# main_board2.net
KiCad netlist of a schematic drawn in Altium Designer
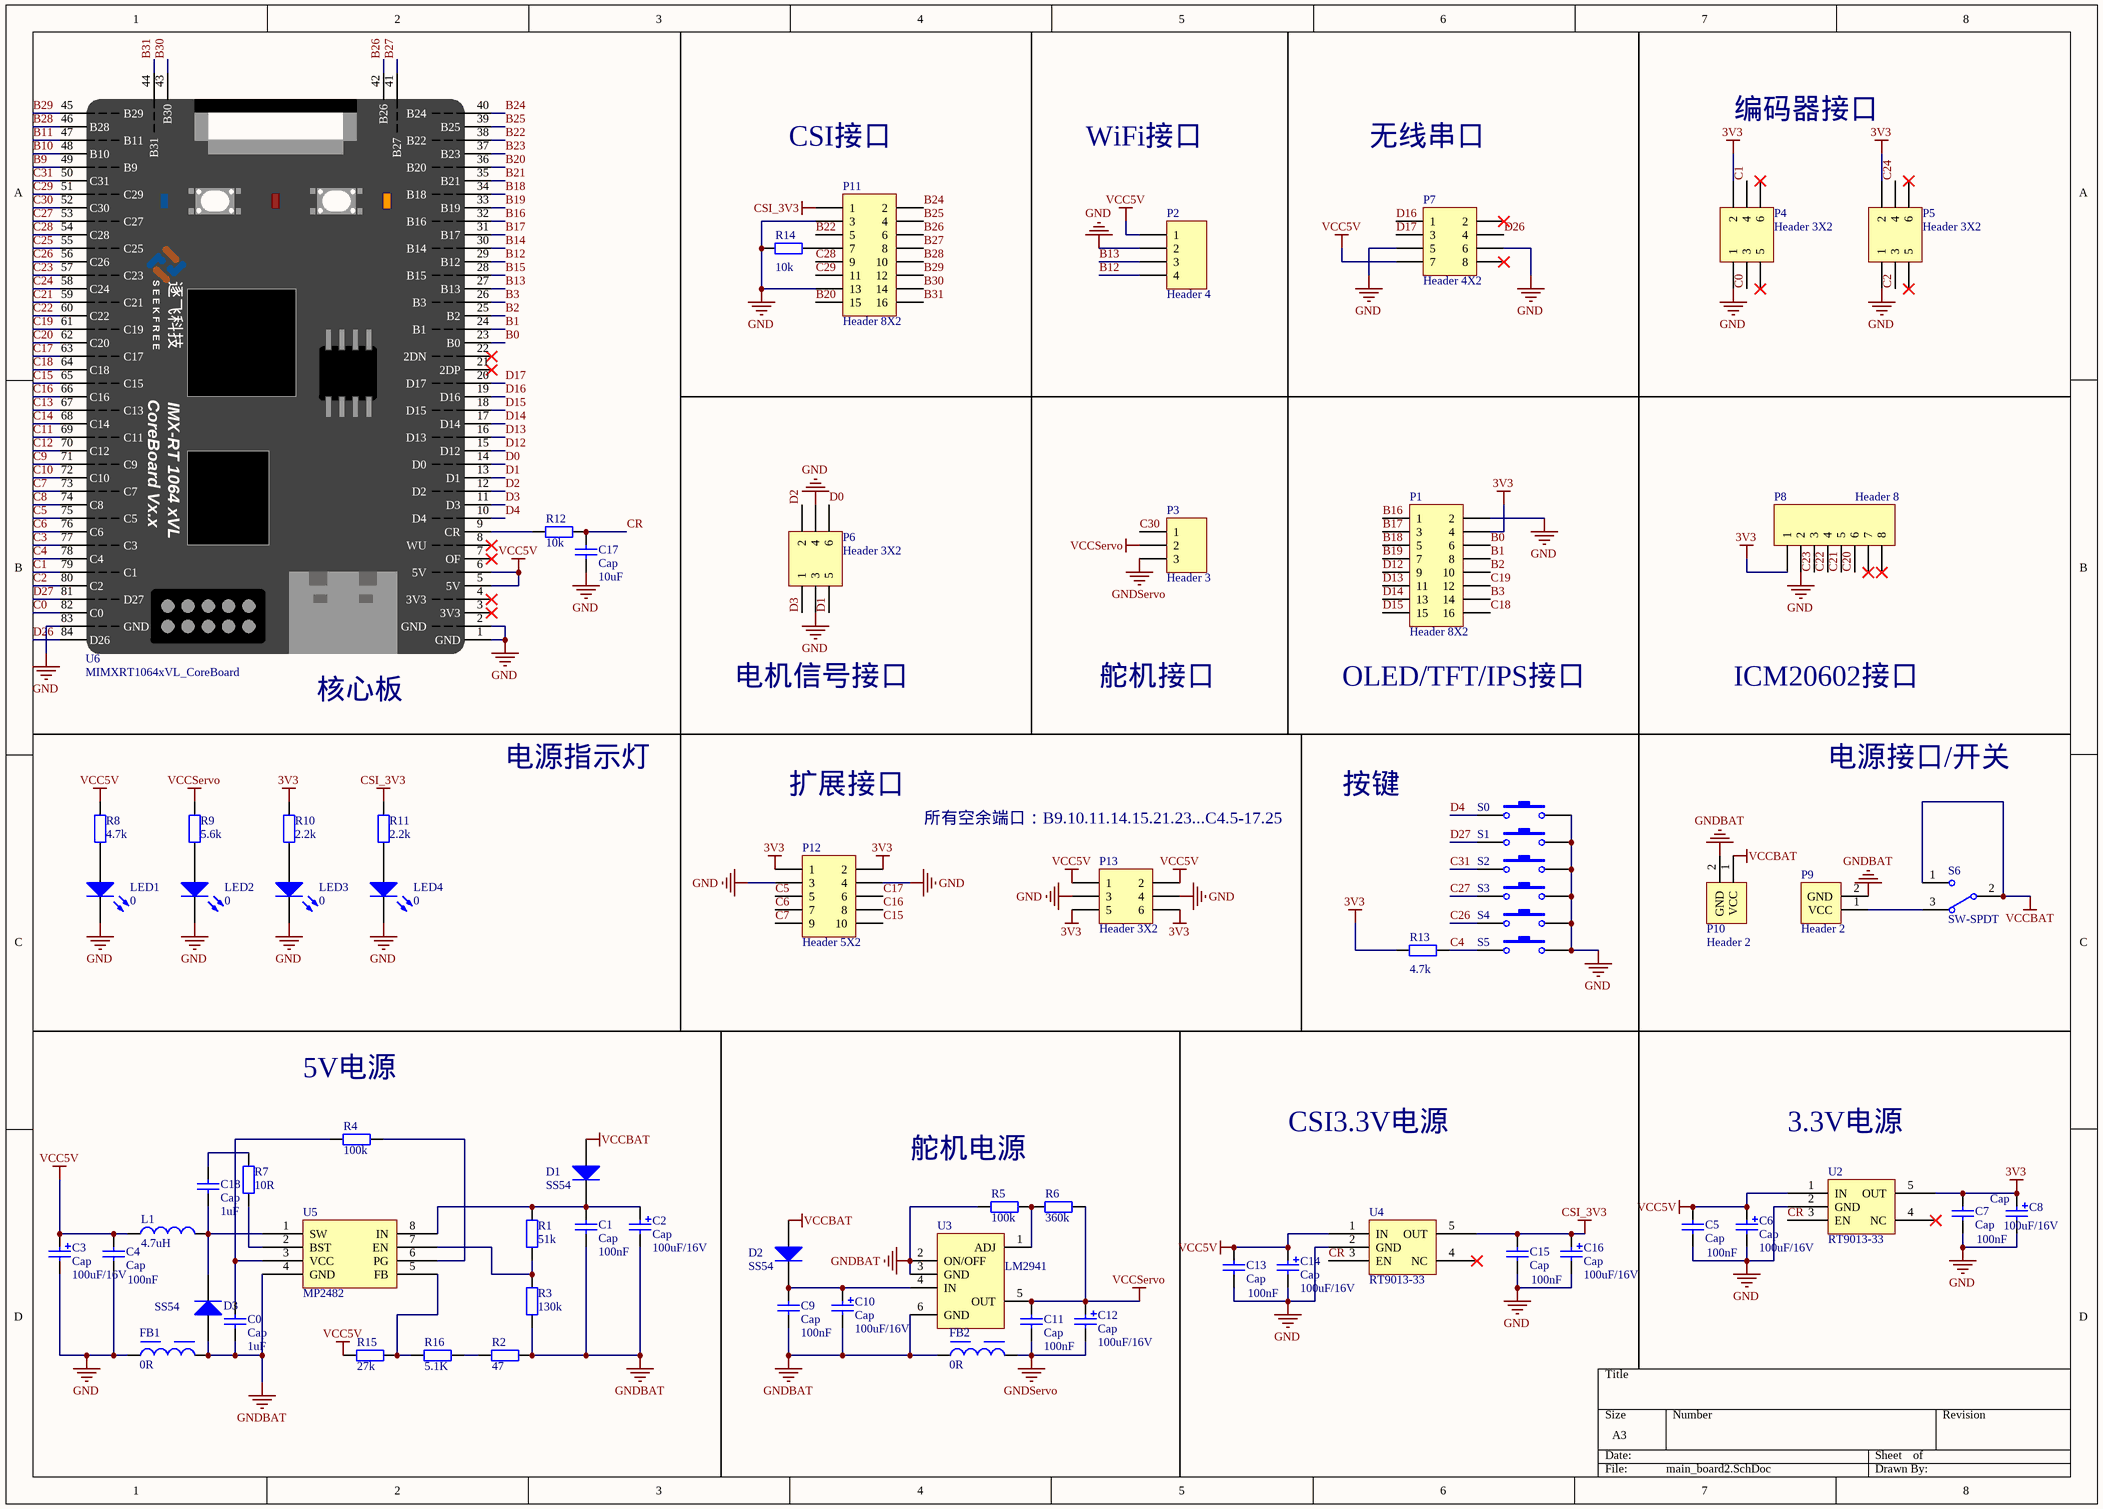
[diagram p0: main_board2.SchDoc]

(export (version "E")
  (design (tool "Eeschema 10.0.6"))
  (components
    (comp (ref "C0")
      (value "Cap")
      (footprint "0603C")
      (description "Capacitor")
      (fields (field (name "ALTIUM_VALUE") "1uF") (field (name "PUBLISHER") "Altium Limited"))
      (libsource (lib "Schlib1") (part "Cap"))
    )
    (comp (ref "C1")
      (value "Cap")
      (footprint "0603C")
      (description "Capacitor")
      (fields (field (name "ALTIUM_VALUE") "100nF") (field (name "PUBLISHER") "Altium Limited"))
      (libsource (lib "Schlib1") (part "Cap"))
    )
    (comp (ref "C2")
      (value "Cap")
      (footprint "电解电容")
      (description "Capacitor")
      (fields (field (name "ALTIUM_VALUE") "100uF/16V") (field (name "PUBLISHER") "Altium Limited"))
      (libsource (lib "Schlib1") (part "Cap2"))
    )
    (comp (ref "C3")
      (value "Cap")
      (footprint "电解电容")
      (description "Capacitor")
      (fields (field (name "ALTIUM_VALUE") "100uF/16V") (field (name "PUBLISHER") "Altium Limited"))
      (libsource (lib "Schlib1") (part "Cap2"))
    )
    (comp (ref "C4")
      (value "Cap")
      (footprint "0603C")
      (description "Capacitor")
      (fields (field (name "ALTIUM_VALUE") "100nF") (field (name "PUBLISHER") "Altium Limited"))
      (libsource (lib "Schlib1") (part "Cap"))
    )
    (comp (ref "C5")
      (value "Cap")
      (footprint "0603C")
      (description "Capacitor")
      (fields (field (name "ALTIUM_VALUE") "100nF") (field (name "PUBLISHER") "Altium Limited"))
      (libsource (lib "Schlib1") (part "Cap"))
    )
    (comp (ref "C6")
      (value "Cap")
      (footprint "电解电容")
      (description "Capacitor")
      (fields (field (name "ALTIUM_VALUE") "100uF/16V") (field (name "PUBLISHER") "Altium Limited"))
      (libsource (lib "Schlib1") (part "Cap2"))
    )
    (comp (ref "C7")
      (value "Cap")
      (footprint "0603C")
      (description "Capacitor")
      (fields (field (name "ALTIUM_VALUE") "100nF") (field (name "PUBLISHER") "Altium Limited"))
      (libsource (lib "Schlib1") (part "Cap"))
    )
    (comp (ref "C8")
      (value "Cap")
      (footprint "电解电容")
      (description "Capacitor")
      (fields (field (name "ALTIUM_VALUE") "100uF/16V") (field (name "PUBLISHER") "Altium Limited"))
      (libsource (lib "Schlib1") (part "Cap2"))
    )
    (comp (ref "C9")
      (value "Cap")
      (footprint "0603C")
      (description "Capacitor")
      (fields (field (name "ALTIUM_VALUE") "100nF") (field (name "PUBLISHER") "Altium Limited"))
      (libsource (lib "Schlib1") (part "Cap"))
    )
    (comp (ref "C10")
      (value "Cap")
      (footprint "电解电容")
      (description "Capacitor")
      (fields (field (name "ALTIUM_VALUE") "100uF/16V") (field (name "PUBLISHER") "Altium Limited"))
      (libsource (lib "Schlib1") (part "Cap2"))
    )
    (comp (ref "C11")
      (value "Cap")
      (footprint "0603C")
      (description "Capacitor")
      (fields (field (name "ALTIUM_VALUE") "100nF") (field (name "PUBLISHER") "Altium Limited"))
      (libsource (lib "Schlib1") (part "Cap"))
    )
    (comp (ref "C12")
      (value "Cap")
      (footprint "电解电容")
      (description "Capacitor")
      (fields (field (name "ALTIUM_VALUE") "100uF/16V") (field (name "PUBLISHER") "Altium Limited"))
      (libsource (lib "Schlib1") (part "Cap2"))
    )
    (comp (ref "C13")
      (value "Cap")
      (footprint "0603C")
      (description "Capacitor")
      (fields (field (name "ALTIUM_VALUE") "100nF") (field (name "PUBLISHER") "Altium Limited"))
      (libsource (lib "Schlib1") (part "Cap"))
    )
    (comp (ref "C14")
      (value "Cap")
      (footprint "电解电容")
      (description "Capacitor")
      (fields (field (name "ALTIUM_VALUE") "100uF/16V") (field (name "PUBLISHER") "Altium Limited"))
      (libsource (lib "Schlib1") (part "Cap2"))
    )
    (comp (ref "C15")
      (value "Cap")
      (footprint "0603C")
      (description "Capacitor")
      (fields (field (name "ALTIUM_VALUE") "100nF") (field (name "PUBLISHER") "Altium Limited"))
      (libsource (lib "Schlib1") (part "Cap"))
    )
    (comp (ref "C16")
      (value "Cap")
      (footprint "电解电容")
      (description "Capacitor")
      (fields (field (name "ALTIUM_VALUE") "100uF/16V") (field (name "PUBLISHER") "Altium Limited"))
      (libsource (lib "Schlib1") (part "Cap2"))
    )
    (comp (ref "C17")
      (value "Cap")
      (footprint "0603C")
      (description "Capacitor")
      (fields (field (name "ALTIUM_VALUE") "10uF") (field (name "PUBLISHER") "Altium Limited"))
      (libsource (lib "Schlib1") (part "Cap"))
    )
    (comp (ref "C18")
      (value "Cap")
      (footprint "0603C")
      (description "Capacitor")
      (fields (field (name "ALTIUM_VALUE") "1uF") (field (name "PUBLISHER") "Altium Limited"))
      (libsource (lib "Schlib1") (part "Cap"))
    )
    (comp (ref "D1")
      (value "SS54")
      (footprint "ss54")
      (description "Default Diode")
      (fields (field (name "PUBLISHER") "Altium Limited"))
      (libsource (lib "Schlib1") (part "Diode_1"))
    )
    (comp (ref "D2")
      (value "SS54")
      (footprint "ss54")
      (description "Default Diode")
      (fields (field (name "PUBLISHER") "Altium Limited"))
      (libsource (lib "Schlib1") (part "Diode_1"))
    )
    (comp (ref "D3")
      (value "SS54")
      (footprint "ss54")
      (description "Default Diode")
      (fields (field (name "PUBLISHER") "Altium Limited"))
      (libsource (lib "Schlib1") (part "Diode_1"))
    )
    (comp (ref "FB1")
      (value "0R")
      (footprint "0805")
      (description "Inductor")
      (fields (field (name "PUBLISHER") "Altium Limited"))
      (libsource (lib "Schlib1") (part "FB"))
    )
    (comp (ref "FB2")
      (value "0R")
      (footprint "0805")
      (description "Inductor")
      (fields (field (name "PUBLISHER") "Altium Limited"))
      (libsource (lib "Schlib1") (part "FB"))
    )
    (comp (ref "L1")
      (value "4.7uH")
      (footprint "CD73")
      (description "Inductor")
      (fields (field (name "PUBLISHER") "Altium Limited"))
      (libsource (lib "Schlib1") (part "Inductor_2"))
    )
    (comp (ref "LED1")
      (value "0")
      (footprint "0603C")
      (description "Typical RED, GREEN, YELLOW, AMBER GaAs LED")
      (fields (field (name "PUBLISHER") "Altium Limited"))
      (libsource (lib "Schlib1") (part "LED2"))
    )
    (comp (ref "LED2")
      (value "0")
      (footprint "0603C")
      (description "Typical RED, GREEN, YELLOW, AMBER GaAs LED")
      (fields (field (name "PUBLISHER") "Altium Limited"))
      (libsource (lib "Schlib1") (part "LED2"))
    )
    (comp (ref "LED3")
      (value "0")
      (footprint "0603C")
      (description "Typical RED, GREEN, YELLOW, AMBER GaAs LED")
      (fields (field (name "PUBLISHER") "Altium Limited"))
      (libsource (lib "Schlib1") (part "LED2"))
    )
    (comp (ref "LED4")
      (value "0")
      (footprint "0603C")
      (description "Typical RED, GREEN, YELLOW, AMBER GaAs LED")
      (fields (field (name "PUBLISHER") "Altium Limited"))
      (libsource (lib "Schlib1") (part "LED2"))
    )
    (comp (ref "P1")
      (value "Header 8X2")
      (footprint "HDR2X8")
      (description "Header, 8-Pin, Dual row")
      (fields (field (name "PUBLISHER") "Altium Limited"))
      (libsource (lib "Miscellaneous Connectors") (part "Header 8X2"))
    )
    (comp (ref "P2")
      (value "Header 4")
      (footprint "HDR1X4")
      (description "Header, 4-Pin")
      (fields (field (name "PUBLISHER") "Altium Limited"))
      (libsource (lib "Miscellaneous Connectors") (part "Header 4"))
    )
    (comp (ref "P3")
      (value "Header 3")
      (footprint "HDR1X3")
      (description "Header, 3-Pin")
      (fields (field (name "PUBLISHER") "Altium Limited"))
      (libsource (lib "Miscellaneous Connectors") (part "Header 3"))
    )
    (comp (ref "P4")
      (value "Header 3X2")
      (footprint "HDR2X3")
      (description "Header, 3-Pin, Dual row")
      (fields (field (name "PUBLISHER") "Altium Limited"))
      (libsource (lib "Miscellaneous Connectors") (part "Header 3X2"))
    )
    (comp (ref "P5")
      (value "Header 3X2")
      (footprint "HDR2X3")
      (description "Header, 3-Pin, Dual row")
      (fields (field (name "PUBLISHER") "Altium Limited"))
      (libsource (lib "Miscellaneous Connectors") (part "Header 3X2"))
    )
    (comp (ref "P6")
      (value "Header 3X2")
      (footprint "HDR2X3")
      (description "Header, 3-Pin, Dual row")
      (fields (field (name "PUBLISHER") "Altium Limited"))
      (libsource (lib "Miscellaneous Connectors") (part "Header 3X2"))
    )
    (comp (ref "P7")
      (value "Header 4X2")
      (footprint "HDR2X4")
      (description "Header, 4-Pin, Dual row")
      (fields (field (name "PUBLISHER") "Altium Limited"))
      (libsource (lib "Miscellaneous Connectors") (part "Header 4X2"))
    )
    (comp (ref "P8")
      (value "Header 8")
      (footprint "HDR1X8")
      (description "Header, 8-Pin")
      (fields (field (name "PUBLISHER") "Altium Limited"))
      (libsource (lib "Miscellaneous Connectors") (part "Header 8"))
    )
    (comp (ref "P9")
      (value "Header 2")
      (footprint "VCCBAT")
      (description "Header, 2-Pin")
      (fields (field (name "PUBLISHER") "Altium Limited"))
      (libsource (lib "Schlib1") (part "Header 2_1"))
    )
    (comp (ref "P10")
      (value "Header 2")
      (footprint "VCCBAT")
      (description "Header, 2-Pin")
      (fields (field (name "PUBLISHER") "Altium Limited"))
      (libsource (lib "Schlib1") (part "Header 2_2"))
    )
    (comp (ref "P11")
      (value "Header 8X2")
      (footprint "HDR2X8")
      (description "Header, 8-Pin, Dual row")
      (fields (field (name "PUBLISHER") "Altium Limited"))
      (libsource (lib "Miscellaneous Connectors") (part "Header 8X2"))
    )
    (comp (ref "P12")
      (value "Header 5X2")
      (footprint "HDR2X5")
      (description "Header, 5-Pin, Dual row")
      (fields (field (name "PUBLISHER") "Altium Limited"))
      (libsource (lib "Miscellaneous Connectors") (part "Header 5X2"))
    )
    (comp (ref "P13")
      (value "Header 3X2")
      (footprint "HDR2X3")
      (description "Header, 3-Pin, Dual row")
      (fields (field (name "PUBLISHER") "Altium Limited"))
      (libsource (lib "") (part "Header 3X2_1"))
    )
    (comp (ref "R1")
      (value "51k")
      (footprint "0603R")
      (description "Resistor")
      (fields (field (name "Comment") "Res2") (field (name "PUBLISHER") "Altium Limited"))
      (libsource (lib "") (part "Res2_2"))
    )
    (comp (ref "R2")
      (value "47")
      (footprint "0603R")
      (description "Resistor")
      (fields (field (name "Comment") "Res2") (field (name "PUBLISHER") "Altium Limited"))
      (libsource (lib "Schlib1") (part "Res2"))
    )
    (comp (ref "R3")
      (value "130k")
      (footprint "0603R")
      (description "Resistor 改成了120k")
      (fields (field (name "Comment") "Res2") (field (name "PUBLISHER") "Altium Limited"))
      (libsource (lib "") (part "Res2_2"))
    )
    (comp (ref "R4")
      (value "100k")
      (footprint "0603R")
      (description "Resistor")
      (fields (field (name "Comment") "Res2") (field (name "PUBLISHER") "Altium Limited"))
      (libsource (lib "Schlib1") (part "Res2"))
    )
    (comp (ref "R5")
      (value "100k")
      (footprint "0603R")
      (description "Resistor")
      (fields (field (name "Comment") "Res2") (field (name "PUBLISHER") "Altium Limited"))
      (libsource (lib "") (part "Res2_1"))
    )
    (comp (ref "R6")
      (value "360k")
      (footprint "0603R")
      (description "Resistor 改成了330k")
      (fields (field (name "Comment") "Res2") (field (name "PUBLISHER") "Altium Limited"))
      (libsource (lib "") (part "Res2_1"))
    )
    (comp (ref "R7")
      (value "10R")
      (footprint "0603R")
      (description "Resistor")
      (fields (field (name "Comment") "Res2") (field (name "PUBLISHER") "Altium Limited"))
      (libsource (lib "") (part "Res2_2"))
    )
    (comp (ref "R8")
      (value "4.7k")
      (footprint "0603R")
      (description "Resistor")
      (fields (field (name "Comment") "Res2") (field (name "PUBLISHER") "Altium Limited"))
      (libsource (lib "") (part "Res2_2"))
    )
    (comp (ref "R9")
      (value "5.6k")
      (footprint "0603R")
      (description "Resistor改成了5.1k")
      (fields (field (name "Comment") "Res2") (field (name "PUBLISHER") "Altium Limited"))
      (libsource (lib "") (part "Res2_2"))
    )
    (comp (ref "R10")
      (value "2.2k")
      (footprint "0603R")
      (description "Resistor")
      (fields (field (name "Comment") "Res2") (field (name "PUBLISHER") "Altium Limited"))
      (libsource (lib "") (part "Res2_2"))
    )
    (comp (ref "R11")
      (value "2.2k")
      (footprint "0603R")
      (description "Resistor")
      (fields (field (name "Comment") "Res2") (field (name "PUBLISHER") "Altium Limited"))
      (libsource (lib "") (part "Res2_2"))
    )
    (comp (ref "R12")
      (value "10k")
      (footprint "0603R")
      (description "Resistor")
      (fields (field (name "Comment") "Res2") (field (name "PUBLISHER") "Altium Limited"))
      (libsource (lib "") (part "Res2_1"))
    )
    (comp (ref "R13")
      (value "4.7k")
      (footprint "0603R")
      (description "Resistor")
      (fields (field (name "Comment") "Res2") (field (name "PUBLISHER") "Altium Limited"))
      (libsource (lib "") (part "Res2_1"))
    )
    (comp (ref "R14")
      (value "10k")
      (footprint "0603R")
      (description "Resistor")
      (fields (field (name "Comment") "Res2") (field (name "PUBLISHER") "Altium Limited"))
      (libsource (lib "") (part "Res2_1"))
    )
    (comp (ref "R15")
      (value "27k")
      (footprint "0603R")
      (description "Resistor")
      (fields (field (name "Comment") "Res2") (field (name "PUBLISHER") "Altium Limited"))
      (libsource (lib "Schlib1") (part "Res2"))
    )
    (comp (ref "R16")
      (value "5.1K")
      (footprint "0603R")
      (description "Resistor")
      (fields (field (name "Comment") "Res2") (field (name "PUBLISHER") "Altium Limited"))
      (libsource (lib "Schlib1") (part "Res2"))
    )
    (comp (ref "S0")
      (value "~")
      (footprint "SPST-2")
      (description "Switch")
      (fields (field (name "PUBLISHER") "Altium Limited"))
      (libsource (lib "Miscellaneous Devices") (part "SW-PB"))
    )
    (comp (ref "S1")
      (value "~")
      (footprint "SPST-2")
      (description "Switch")
      (fields (field (name "PUBLISHER") "Altium Limited"))
      (libsource (lib "Miscellaneous Devices") (part "SW-PB"))
    )
    (comp (ref "S2")
      (value "~")
      (footprint "SPST-2")
      (description "Switch")
      (fields (field (name "PUBLISHER") "Altium Limited"))
      (libsource (lib "Miscellaneous Devices") (part "SW-PB"))
    )
    (comp (ref "S3")
      (value "~")
      (footprint "SPST-2")
      (description "Switch")
      (fields (field (name "PUBLISHER") "Altium Limited"))
      (libsource (lib "Miscellaneous Devices") (part "SW-PB"))
    )
    (comp (ref "S4")
      (value "~")
      (footprint "SPST-2")
      (description "Switch")
      (fields (field (name "PUBLISHER") "Altium Limited"))
      (libsource (lib "Miscellaneous Devices") (part "SW-PB"))
    )
    (comp (ref "S5")
      (value "~")
      (footprint "SPST-2")
      (description "Switch")
      (fields (field (name "PUBLISHER") "Altium Limited"))
      (libsource (lib "Miscellaneous Devices") (part "SW-PB"))
    )
    (comp (ref "S6")
      (value "SW-SPDT")
      (footprint "SW")
      (description "SPDT Subminiature Toggle Switch, Right Angle Mounting, Vertical Actuation")
      (fields (field (name "PUBLISHER") "Altium Limited"))
      (libsource (lib "Miscellaneous Devices") (part "SW-SPDT"))
    )
    (comp (ref "U2")
      (value "RT9013-33")
      (footprint "SOT23-5_L")
      (libsource (lib "Schlib1") (part "RT9013-33"))
    )
    (comp (ref "U3")
      (value "LM2941")
      (footprint "TO-263-5L")
      (description "Header, 4-Pin")
      (fields (field (name "PUBLISHER") "Altium Limited"))
      (libsource (lib "Schlib1") (part "LM2941"))
    )
    (comp (ref "U4")
      (value "RT9013-33")
      (footprint "SOT23-5_L")
      (libsource (lib "Schlib1") (part "RT9013-33"))
    )
    (comp (ref "U5") (value "MP2482") (footprint "Motor:SOIC-8") (libsource (lib "Schlib1") (part "MP2482")))
    (comp (ref "U6")
      (value "MIMXRT1064xVL_CoreBoard")
      (footprint "MIMXRT1064xVL_CoreBoard")
      (description "逐飞科技i.MX RT1064核心板整体原理，可直接使用")
      (libsource (lib "RT1064 V1.2核心板原理库") (part "MIMXRT1064xVL_CoreBoard"))
    )
  )
  (nets
    (net (code "1") (name "/B0") (class "Default")
      (node (ref "P1") (pin "6") (pinfunction "6_6") (pintype "passive"))
      (node (ref "U6") (pin "23") (pinfunction "B0_23") (pintype "passive"))
    )
    (net (code "2") (name "/B1") (class "Default")
      (node (ref "P1") (pin "8") (pinfunction "8_8") (pintype "passive"))
      (node (ref "U6") (pin "24") (pinfunction "B1_24") (pintype "passive"))
    )
    (net (code "3") (name "/B2") (class "Default")
      (node (ref "P1") (pin "10") (pinfunction "10_10") (pintype "passive"))
      (node (ref "U6") (pin "25") (pinfunction "B2_25") (pintype "passive"))
    )
    (net (code "4") (name "/B3") (class "Default")
      (node (ref "P1") (pin "14") (pinfunction "14_14") (pintype "passive"))
      (node (ref "U6") (pin "26") (pinfunction "B3_26") (pintype "passive"))
    )
    (net (code "5") (name "/B9") (class "Default")
      (node (ref "U6") (pin "49") (pinfunction "B9_49") (pintype "passive"))
    )
    (net (code "6") (name "/B10") (class "Default")
      (node (ref "U6") (pin "48") (pinfunction "B10_48") (pintype "passive"))
    )
    (net (code "7") (name "/B11") (class "Default")
      (node (ref "U6") (pin "47") (pinfunction "B11_47") (pintype "passive"))
    )
    (net (code "8") (name "/B12") (class "Default")
      (node (ref "P2") (pin "4") (pinfunction "4_4") (pintype "passive"))
      (node (ref "U6") (pin "29") (pinfunction "B12_29") (pintype "passive"))
    )
    (net (code "9") (name "/B13") (class "Default")
      (node (ref "P2") (pin "3") (pinfunction "3_3") (pintype "passive"))
      (node (ref "U6") (pin "27") (pinfunction "B13_27") (pintype "passive"))
    )
    (net (code "10") (name "/B14") (class "Default")
      (node (ref "U6") (pin "30") (pinfunction "B14_30") (pintype "passive"))
    )
    (net (code "11") (name "/B15") (class "Default")
      (node (ref "U6") (pin "28") (pinfunction "B15_28") (pintype "passive"))
    )
    (net (code "12") (name "/B16") (class "Default")
      (node (ref "P1") (pin "1") (pinfunction "1_1") (pintype "passive"))
      (node (ref "U6") (pin "32") (pinfunction "B16_32") (pintype "passive"))
    )
    (net (code "13") (name "/B17") (class "Default")
      (node (ref "P1") (pin "3") (pinfunction "3_3") (pintype "passive"))
      (node (ref "U6") (pin "31") (pinfunction "B17_31") (pintype "passive"))
    )
    (net (code "14") (name "/B18") (class "Default")
      (node (ref "P1") (pin "5") (pinfunction "5_5") (pintype "passive"))
      (node (ref "U6") (pin "34") (pinfunction "B18_34") (pintype "passive"))
    )
    (net (code "15") (name "/B19") (class "Default")
      (node (ref "P1") (pin "7") (pinfunction "7_7") (pintype "passive"))
      (node (ref "U6") (pin "33") (pinfunction "B19_33") (pintype "passive"))
    )
    (net (code "16") (name "/B20") (class "Default")
      (node (ref "P11") (pin "15") (pinfunction "15_15") (pintype "passive"))
      (node (ref "U6") (pin "36") (pinfunction "B20_36") (pintype "passive"))
    )
    (net (code "17") (name "/B21") (class "Default")
      (node (ref "U6") (pin "35") (pinfunction "B21_35") (pintype "passive"))
    )
    (net (code "18") (name "/B22") (class "Default")
      (node (ref "P11") (pin "5") (pinfunction "5_5") (pintype "passive"))
      (node (ref "U6") (pin "38") (pinfunction "B22_38") (pintype "passive"))
    )
    (net (code "19") (name "/B23") (class "Default")
      (node (ref "U6") (pin "37") (pinfunction "B23_37") (pintype "passive"))
    )
    (net (code "20") (name "/B24") (class "Default")
      (node (ref "P11") (pin "2") (pinfunction "2_2") (pintype "passive"))
      (node (ref "U6") (pin "40") (pinfunction "B24_40") (pintype "passive"))
    )
    (net (code "21") (name "/B25") (class "Default")
      (node (ref "P11") (pin "4") (pinfunction "4_4") (pintype "passive"))
      (node (ref "U6") (pin "39") (pinfunction "B25_39") (pintype "passive"))
    )
    (net (code "22") (name "/B26") (class "Default")
      (node (ref "P11") (pin "6") (pinfunction "6_6") (pintype "passive"))
      (node (ref "U6") (pin "42") (pinfunction "B26_42") (pintype "passive"))
    )
    (net (code "23") (name "/B27") (class "Default")
      (node (ref "P11") (pin "8") (pinfunction "8_8") (pintype "passive"))
      (node (ref "U6") (pin "41") (pinfunction "B27_41") (pintype "passive"))
    )
    (net (code "24") (name "/B28") (class "Default")
      (node (ref "P11") (pin "10") (pinfunction "10_10") (pintype "passive"))
      (node (ref "U6") (pin "46") (pinfunction "B28_46") (pintype "passive"))
    )
    (net (code "25") (name "/B29") (class "Default")
      (node (ref "P11") (pin "12") (pinfunction "12_12") (pintype "passive"))
      (node (ref "U6") (pin "45") (pinfunction "B29_45") (pintype "passive"))
    )
    (net (code "26") (name "/B30") (class "Default")
      (node (ref "P11") (pin "14") (pinfunction "14_14") (pintype "passive"))
      (node (ref "U6") (pin "43") (pinfunction "B30_43") (pintype "passive"))
    )
    (net (code "27") (name "/B31") (class "Default")
      (node (ref "P11") (pin "16") (pinfunction "16_16") (pintype "passive"))
      (node (ref "U6") (pin "44") (pinfunction "B31_44") (pintype "passive"))
    )
    (net (code "28") (name "/C0") (class "Default")
      (node (ref "P4") (pin "3") (pinfunction "3_3") (pintype "passive"))
      (node (ref "U6") (pin "82") (pinfunction "C0_82") (pintype "passive"))
    )
    (net (code "29") (name "/C1") (class "Default")
      (node (ref "P4") (pin "4") (pinfunction "4_4") (pintype "passive"))
      (node (ref "U6") (pin "79") (pinfunction "C1_79") (pintype "passive"))
    )
    (net (code "30") (name "/C2") (class "Default")
      (node (ref "P5") (pin "3") (pinfunction "3_3") (pintype "passive"))
      (node (ref "U6") (pin "80") (pinfunction "C2_80") (pintype "passive"))
    )
    (net (code "31") (name "/C3") (class "Default")
      (node (ref "U6") (pin "77") (pinfunction "C3_77") (pintype "passive"))
    )
    (net (code "32") (name "/C4") (class "Default")
      (node (ref "R13") (pin "2") (pinfunction "2_2") (pintype "passive"))
      (node (ref "S5") (pin "1") (pinfunction "1_1") (pintype "passive"))
      (node (ref "U6") (pin "78") (pinfunction "C4_78") (pintype "passive"))
    )
    (net (code "33") (name "/C5") (class "Default")
      (node (ref "P12") (pin "5") (pinfunction "5_5") (pintype "passive"))
      (node (ref "U6") (pin "75") (pinfunction "C5_75") (pintype "passive"))
    )
    (net (code "34") (name "/C6") (class "Default")
      (node (ref "P12") (pin "7") (pinfunction "7_7") (pintype "passive"))
      (node (ref "U6") (pin "76") (pinfunction "C6_76") (pintype "passive"))
    )
    (net (code "35") (name "/C7") (class "Default")
      (node (ref "P12") (pin "9") (pinfunction "9_9") (pintype "passive"))
      (node (ref "U6") (pin "73") (pinfunction "C7_73") (pintype "passive"))
    )
    (net (code "36") (name "/C8") (class "Default")
      (node (ref "U6") (pin "74") (pinfunction "C8_74") (pintype "passive"))
    )
    (net (code "37") (name "/C9") (class "Default")
      (node (ref "U6") (pin "71") (pinfunction "C9_71") (pintype "passive"))
    )
    (net (code "38") (name "/C10") (class "Default")
      (node (ref "U6") (pin "72") (pinfunction "C10_72") (pintype "passive"))
    )
    (net (code "39") (name "/C11") (class "Default")
      (node (ref "U6") (pin "69") (pinfunction "C11_69") (pintype "passive"))
    )
    (net (code "40") (name "/C12") (class "Default")
      (node (ref "U6") (pin "70") (pinfunction "C12_70") (pintype "passive"))
    )
    (net (code "41") (name "/C13") (class "Default")
      (node (ref "U6") (pin "67") (pinfunction "C13_67") (pintype "passive"))
    )
    (net (code "42") (name "/C14") (class "Default")
      (node (ref "U6") (pin "68") (pinfunction "C14_68") (pintype "passive"))
    )
    (net (code "43") (name "/C15") (class "Default")
      (node (ref "P12") (pin "10") (pinfunction "10_10") (pintype "passive"))
      (node (ref "U6") (pin "65") (pinfunction "C15_65") (pintype "passive"))
    )
    (net (code "44") (name "/C16") (class "Default")
      (node (ref "P12") (pin "8") (pinfunction "8_8") (pintype "passive"))
      (node (ref "U6") (pin "66") (pinfunction "C16_66") (pintype "passive"))
    )
    (net (code "45") (name "/C17") (class "Default")
      (node (ref "P12") (pin "6") (pinfunction "6_6") (pintype "passive"))
      (node (ref "U6") (pin "63") (pinfunction "C17_63") (pintype "passive"))
    )
    (net (code "46") (name "/C18") (class "Default")
      (node (ref "P1") (pin "16") (pinfunction "16_16") (pintype "passive"))
      (node (ref "U6") (pin "64") (pinfunction "C18_64") (pintype "passive"))
    )
    (net (code "47") (name "/C19") (class "Default")
      (node (ref "P1") (pin "12") (pinfunction "12_12") (pintype "passive"))
      (node (ref "U6") (pin "61") (pinfunction "C19_61") (pintype "passive"))
    )
    (net (code "48") (name "/C20") (class "Default")
      (node (ref "P8") (pin "6") (pinfunction "6_6") (pintype "passive"))
      (node (ref "U6") (pin "62") (pinfunction "C20_62") (pintype "passive"))
    )
    (net (code "49") (name "/C21") (class "Default")
      (node (ref "P8") (pin "5") (pinfunction "5_5") (pintype "passive"))
      (node (ref "U6") (pin "59") (pinfunction "C21_59") (pintype "passive"))
    )
    (net (code "50") (name "/C22") (class "Default")
      (node (ref "P8") (pin "4") (pinfunction "4_4") (pintype "passive"))
      (node (ref "U6") (pin "60") (pinfunction "C22_60") (pintype "passive"))
    )
    (net (code "51") (name "/C23") (class "Default")
      (node (ref "P8") (pin "3") (pinfunction "3_3") (pintype "passive"))
      (node (ref "U6") (pin "57") (pinfunction "C23_57") (pintype "passive"))
    )
    (net (code "52") (name "/C24") (class "Default")
      (node (ref "P5") (pin "4") (pinfunction "4_4") (pintype "passive"))
      (node (ref "U6") (pin "58") (pinfunction "C24_58") (pintype "passive"))
    )
    (net (code "53") (name "/C25") (class "Default")
      (node (ref "U6") (pin "55") (pinfunction "C25_55") (pintype "passive"))
    )
    (net (code "54") (name "/C26") (class "Default")
      (node (ref "S4") (pin "1") (pinfunction "1_1") (pintype "passive"))
      (node (ref "U6") (pin "56") (pinfunction "C26_56") (pintype "passive"))
    )
    (net (code "55") (name "/C27") (class "Default")
      (node (ref "S3") (pin "1") (pinfunction "1_1") (pintype "passive"))
      (node (ref "U6") (pin "53") (pinfunction "C27_53") (pintype "passive"))
    )
    (net (code "56") (name "/C28") (class "Default")
      (node (ref "P11") (pin "9") (pinfunction "9_9") (pintype "passive"))
      (node (ref "U6") (pin "54") (pinfunction "C28_54") (pintype "passive"))
    )
    (net (code "57") (name "/C29") (class "Default")
      (node (ref "P11") (pin "11") (pinfunction "11_11") (pintype "passive"))
      (node (ref "U6") (pin "51") (pinfunction "C29_51") (pintype "passive"))
    )
    (net (code "58") (name "/C30") (class "Default")
      (node (ref "P3") (pin "1") (pinfunction "1_1") (pintype "passive"))
      (node (ref "U6") (pin "52") (pinfunction "C30_52") (pintype "passive"))
    )
    (net (code "59") (name "/C31") (class "Default")
      (node (ref "S2") (pin "1") (pinfunction "1_1") (pintype "passive"))
      (node (ref "U6") (pin "50") (pinfunction "C31_50") (pintype "passive"))
    )
    (net (code "60") (name "/CR") (class "Default")
      (node (ref "C17") (pin "2") (pinfunction "2_2") (pintype "passive"))
      (node (ref "R12") (pin "2") (pinfunction "2_2") (pintype "passive"))
      (node (ref "U2") (pin "3") (pinfunction "EN_3") (pintype "passive"))
      (node (ref "U4") (pin "3") (pinfunction "EN_3") (pintype "passive"))
    )
    (net (code "61") (name "/D0") (class "Default")
      (node (ref "P6") (pin "6") (pinfunction "6_6") (pintype "passive"))
      (node (ref "U6") (pin "14") (pinfunction "D0_14") (pintype "passive"))
    )
    (net (code "62") (name "/D1") (class "Default")
      (node (ref "P6") (pin "5") (pinfunction "5_5") (pintype "passive"))
      (node (ref "U6") (pin "13") (pinfunction "D1_13") (pintype "passive"))
    )
    (net (code "63") (name "/D2") (class "Default")
      (node (ref "P6") (pin "2") (pinfunction "2_2") (pintype "passive"))
      (node (ref "U6") (pin "12") (pinfunction "D2_12") (pintype "passive"))
    )
    (net (code "64") (name "/D3") (class "Default")
      (node (ref "P6") (pin "1") (pinfunction "1_1") (pintype "passive"))
      (node (ref "U6") (pin "11") (pinfunction "D3_11") (pintype "passive"))
    )
    (net (code "65") (name "/D4") (class "Default")
      (node (ref "S0") (pin "1") (pinfunction "1_1") (pintype "passive"))
      (node (ref "U6") (pin "10") (pinfunction "D4_10") (pintype "passive"))
    )
    (net (code "66") (name "/D12") (class "Default")
      (node (ref "P1") (pin "9") (pinfunction "9_9") (pintype "passive"))
      (node (ref "U6") (pin "15") (pinfunction "D12_15") (pintype "passive"))
    )
    (net (code "67") (name "/D13") (class "Default")
      (node (ref "P1") (pin "11") (pinfunction "11_11") (pintype "passive"))
      (node (ref "U6") (pin "16") (pinfunction "D13_16") (pintype "passive"))
    )
    (net (code "68") (name "/D14") (class "Default")
      (node (ref "P1") (pin "13") (pinfunction "13_13") (pintype "passive"))
      (node (ref "U6") (pin "17") (pinfunction "D14_17") (pintype "passive"))
    )
    (net (code "69") (name "/D15") (class "Default")
      (node (ref "P1") (pin "15") (pinfunction "15_15") (pintype "passive"))
      (node (ref "U6") (pin "18") (pinfunction "D15_18") (pintype "passive"))
    )
    (net (code "70") (name "/D16") (class "Default")
      (node (ref "P7") (pin "1") (pinfunction "1_1") (pintype "passive"))
      (node (ref "U6") (pin "19") (pinfunction "D16_19") (pintype "passive"))
    )
    (net (code "71") (name "/D17") (class "Default")
      (node (ref "P7") (pin "3") (pinfunction "3_3") (pintype "passive"))
      (node (ref "U6") (pin "20") (pinfunction "D17_20") (pintype "passive"))
    )
    (net (code "72") (name "/D26") (class "Default")
      (node (ref "P7") (pin "4") (pinfunction "4_4") (pintype "passive"))
      (node (ref "U6") (pin "84") (pinfunction "D26_84") (pintype "passive"))
    )
    (net (code "73") (name "/D27") (class "Default")
      (node (ref "S1") (pin "1") (pinfunction "1_1") (pintype "passive"))
      (node (ref "U6") (pin "81") (pinfunction "D27_81") (pintype "passive"))
    )
    (net (code "74") (name "3V3") (class "Default")
      (node (ref "C7") (pin "2") (pinfunction "2_2") (pintype "passive"))
      (node (ref "C8") (pin "1") (pinfunction "1_1") (pintype "passive"))
      (node (ref "P1") (pin "4") (pinfunction "4_4") (pintype "passive"))
      (node (ref "P12") (pin "1") (pinfunction "1_1") (pintype "passive"))
      (node (ref "P12") (pin "2") (pinfunction "2_2") (pintype "passive"))
      (node (ref "P13") (pin "5") (pinfunction "5_5") (pintype "passive"))
      (node (ref "P13") (pin "6") (pinfunction "6_6") (pintype "passive"))
      (node (ref "P4") (pin "2") (pinfunction "2_2") (pintype "passive"))
      (node (ref "P5") (pin "2") (pinfunction "2_2") (pintype "passive"))
      (node (ref "P8") (pin "1") (pinfunction "1_1") (pintype "passive"))
      (node (ref "R10") (pin "2") (pinfunction "2_2") (pintype "passive"))
      (node (ref "R13") (pin "1") (pinfunction "1_1") (pintype "passive"))
      (node (ref "U2") (pin "5") (pinfunction "OUT_5") (pintype "passive"))
    )
    (net (code "75") (name "CSI_3V3") (class "Default")
      (node (ref "C15") (pin "2") (pinfunction "2_2") (pintype "passive"))
      (node (ref "C16") (pin "1") (pinfunction "1_1") (pintype "passive"))
      (node (ref "P11") (pin "1") (pinfunction "1_1") (pintype "passive"))
      (node (ref "R11") (pin "2") (pinfunction "2_2") (pintype "passive"))
      (node (ref "U4") (pin "5") (pinfunction "OUT_5") (pintype "passive"))
    )
    (net (code "76") (name "GND") (class "Default")
      (node (ref "C13") (pin "1") (pinfunction "1_1") (pintype "passive"))
      (node (ref "C14") (pin "2") (pinfunction "2_2") (pintype "passive"))
      (node (ref "C15") (pin "1") (pinfunction "1_1") (pintype "passive"))
      (node (ref "C16") (pin "2") (pinfunction "2_2") (pintype "passive"))
      (node (ref "C17") (pin "1") (pinfunction "1_1") (pintype "passive"))
      (node (ref "C3") (pin "2") (pinfunction "2_2") (pintype "passive"))
      (node (ref "C4") (pin "1") (pinfunction "1_1") (pintype "passive"))
      (node (ref "C5") (pin "1") (pinfunction "1_1") (pintype "passive"))
      (node (ref "C6") (pin "2") (pinfunction "2_2") (pintype "passive"))
      (node (ref "C7") (pin "1") (pinfunction "1_1") (pintype "passive"))
      (node (ref "C8") (pin "2") (pinfunction "2_2") (pintype "passive"))
      (node (ref "FB1") (pin "1") (pinfunction "1_1") (pintype "passive"))
      (node (ref "LED1") (pin "2") (pinfunction "K_2") (pintype "passive"))
      (node (ref "LED2") (pin "2") (pinfunction "K_2") (pintype "passive"))
      (node (ref "LED3") (pin "2") (pinfunction "K_2") (pintype "passive"))
      (node (ref "LED4") (pin "2") (pinfunction "K_2") (pintype "passive"))
      (node (ref "P1") (pin "2") (pinfunction "2_2") (pintype "passive"))
      (node (ref "P11") (pin "13") (pinfunction "13_13") (pintype "passive"))
      (node (ref "P11") (pin "3") (pinfunction "3_3") (pintype "passive"))
      (node (ref "P12") (pin "3") (pinfunction "3_3") (pintype "passive"))
      (node (ref "P12") (pin "4") (pinfunction "4_4") (pintype "passive"))
      (node (ref "P13") (pin "3") (pinfunction "3_3") (pintype "passive"))
      (node (ref "P13") (pin "4") (pinfunction "4_4") (pintype "passive"))
      (node (ref "P2") (pin "2") (pinfunction "2_2") (pintype "passive"))
      (node (ref "P4") (pin "1") (pinfunction "1_1") (pintype "passive"))
      (node (ref "P5") (pin "1") (pinfunction "1_1") (pintype "passive"))
      (node (ref "P6") (pin "3") (pinfunction "3_3") (pintype "passive"))
      (node (ref "P6") (pin "4") (pinfunction "4_4") (pintype "passive"))
      (node (ref "P7") (pin "5") (pinfunction "5_5") (pintype "passive"))
      (node (ref "P7") (pin "6") (pinfunction "6_6") (pintype "passive"))
      (node (ref "P8") (pin "2") (pinfunction "2_2") (pintype "passive"))
      (node (ref "R14") (pin "1") (pinfunction "1_1") (pintype "passive"))
      (node (ref "S0") (pin "2") (pinfunction "2_2") (pintype "passive"))
      (node (ref "S1") (pin "2") (pinfunction "2_2") (pintype "passive"))
      (node (ref "S2") (pin "2") (pinfunction "2_2") (pintype "passive"))
      (node (ref "S3") (pin "2") (pinfunction "2_2") (pintype "passive"))
      (node (ref "S4") (pin "2") (pinfunction "2_2") (pintype "passive"))
      (node (ref "S5") (pin "2") (pinfunction "2_2") (pintype "passive"))
      (node (ref "U2") (pin "2") (pinfunction "GND_2") (pintype "passive"))
      (node (ref "U4") (pin "2") (pinfunction "GND_2") (pintype "passive"))
      (node (ref "U6") (pin "1") (pinfunction "GND_1") (pintype "passive"))
      (node (ref "U6") (pin "2") (pinfunction "GND_2") (pintype "passive"))
      (node (ref "U6") (pin "83") (pinfunction "GND_83") (pintype "passive"))
    )
    (net (code "77") (name "GNDBAT") (class "Default")
      (node (ref "C0") (pin "2") (pinfunction "2_2") (pintype "passive"))
      (node (ref "C1") (pin "1") (pinfunction "1_1") (pintype "passive"))
      (node (ref "C10") (pin "2") (pinfunction "2_2") (pintype "passive"))
      (node (ref "C2") (pin "2") (pinfunction "2_2") (pintype "passive"))
      (node (ref "C9") (pin "1") (pinfunction "1_1") (pintype "passive"))
      (node (ref "D3") (pin "1") (pinfunction "A_1") (pintype "passive"))
      (node (ref "FB1") (pin "2") (pinfunction "2_2") (pintype "passive"))
      (node (ref "FB2") (pin "1") (pinfunction "1_1") (pintype "passive"))
      (node (ref "P10") (pin "2") (pinfunction "GND_2") (pintype "passive"))
      (node (ref "P9") (pin "2") (pinfunction "GND_2") (pintype "passive"))
      (node (ref "R2") (pin "1") (pinfunction "1_1") (pintype "passive"))
      (node (ref "R3") (pin "1") (pinfunction "1_1") (pintype "passive"))
      (node (ref "R5") (pin "1") (pinfunction "1_1") (pintype "passive"))
      (node (ref "U3") (pin "2") (pinfunction "ON/OFF_2") (pintype "passive"))
      (node (ref "U3") (pin "3") (pinfunction "GND_3") (pintype "passive"))
      (node (ref "U3") (pin "6") (pinfunction "GND_6") (pintype "passive"))
      (node (ref "U5") (pin "4") (pinfunction "GND_4") (pintype "passive"))
    )
    (net (code "78") (name "GNDServo") (class "Default")
      (node (ref "C11") (pin "1") (pinfunction "1_1") (pintype "passive"))
      (node (ref "C12") (pin "2") (pinfunction "2_2") (pintype "passive"))
      (node (ref "FB2") (pin "2") (pinfunction "2_2") (pintype "passive"))
      (node (ref "P3") (pin "3") (pinfunction "3_3") (pintype "passive"))
    )
    (net (code "79") (name "Net-(C18-Pad1)") (class "Default")
      (node (ref "C18") (pin "1") (pinfunction "1_1") (pintype "passive"))
      (node (ref "R7") (pin "2") (pinfunction "2_2") (pintype "passive"))
    )
    (net (code "80") (name "Net-(D1-K)") (class "Default")
      (node (ref "C1") (pin "2") (pinfunction "2_2") (pintype "passive"))
      (node (ref "C2") (pin "1") (pinfunction "1_1") (pintype "passive"))
      (node (ref "D1") (pin "2") (pinfunction "K_2") (pintype "passive"))
      (node (ref "R1") (pin "2") (pinfunction "2_2") (pintype "passive"))
      (node (ref "U5") (pin "8") (pinfunction "IN_8") (pintype "passive"))
    )
    (net (code "81") (name "Net-(D2-K)") (class "Default")
      (node (ref "C10") (pin "1") (pinfunction "1_1") (pintype "passive"))
      (node (ref "C9") (pin "2") (pinfunction "2_2") (pintype "passive"))
      (node (ref "D2") (pin "2") (pinfunction "K_2") (pintype "passive"))
      (node (ref "U3") (pin "4") (pinfunction "IN_4") (pintype "passive"))
    )
    (net (code "82") (name "Net-(D3-K)") (class "Default")
      (node (ref "C18") (pin "2") (pinfunction "2_2") (pintype "passive"))
      (node (ref "D3") (pin "2") (pinfunction "K_2") (pintype "passive"))
      (node (ref "L1") (pin "2") (pinfunction "2_2") (pintype "passive"))
      (node (ref "U5") (pin "1") (pinfunction "SW_1") (pintype "passive"))
    )
    (net (code "83") (name "Net-(LED1-A)") (class "Default")
      (node (ref "LED1") (pin "1") (pinfunction "A_1") (pintype "passive"))
      (node (ref "R8") (pin "1") (pinfunction "1_1") (pintype "passive"))
    )
    (net (code "84") (name "Net-(LED2-A)") (class "Default")
      (node (ref "LED2") (pin "1") (pinfunction "A_1") (pintype "passive"))
      (node (ref "R9") (pin "1") (pinfunction "1_1") (pintype "passive"))
    )
    (net (code "85") (name "Net-(LED3-A)") (class "Default")
      (node (ref "LED3") (pin "1") (pinfunction "A_1") (pintype "passive"))
      (node (ref "R10") (pin "1") (pinfunction "1_1") (pintype "passive"))
    )
    (net (code "86") (name "Net-(LED4-A)") (class "Default")
      (node (ref "LED4") (pin "1") (pinfunction "A_1") (pintype "passive"))
      (node (ref "R11") (pin "1") (pinfunction "1_1") (pintype "passive"))
    )
    (net (code "87") (name "Net-(P9-VCC)") (class "Default")
      (node (ref "P9") (pin "1") (pinfunction "VCC_1") (pintype "passive"))
      (node (ref "S6") (pin "3") (pinfunction "3_3") (pintype "passive"))
    )
    (net (code "88") (name "Net-(P11-Pad7)") (class "Default")
      (node (ref "P11") (pin "7") (pinfunction "7_7") (pintype "passive"))
      (node (ref "R14") (pin "2") (pinfunction "2_2") (pintype "passive"))
    )
    (net (code "89") (name "Net-(R16-Pad1)") (class "Default")
      (node (ref "R16") (pin "1") (pinfunction "1_1") (pintype "passive"))
      (node (ref "R2") (pin "2") (pinfunction "2_2") (pintype "passive"))
    )
    (net (code "90") (name "Net-(U3-ADJ)") (class "Default")
      (node (ref "R5") (pin "2") (pinfunction "2_2") (pintype "passive"))
      (node (ref "R6") (pin "1") (pinfunction "1_1") (pintype "passive"))
      (node (ref "U3") (pin "1") (pinfunction "ADJ_1") (pintype "passive"))
    )
    (net (code "91") (name "Net-(U5-BST)") (class "Default")
      (node (ref "R7") (pin "1") (pinfunction "1_1") (pintype "passive"))
      (node (ref "U5") (pin "2") (pinfunction "BST_2") (pintype "passive"))
    )
    (net (code "92") (name "Net-(U5-EN)") (class "Default")
      (node (ref "R1") (pin "1") (pinfunction "1_1") (pintype "passive"))
      (node (ref "R3") (pin "2") (pinfunction "2_2") (pintype "passive"))
      (node (ref "U5") (pin "7") (pinfunction "EN_7") (pintype "passive"))
    )
    (net (code "93") (name "Net-(U5-FB)") (class "Default")
      (node (ref "R15") (pin "1") (pinfunction "1_1") (pintype "passive"))
      (node (ref "R16") (pin "2") (pinfunction "2_2") (pintype "passive"))
      (node (ref "U5") (pin "5") (pinfunction "FB_5") (pintype "passive"))
    )
    (net (code "94") (name "Net-(U5-PG)") (class "Default")
      (node (ref "R4") (pin "1") (pinfunction "1_1") (pintype "passive"))
      (node (ref "U5") (pin "6") (pinfunction "PG_6") (pintype "passive"))
    )
    (net (code "95") (name "Net-(U5-VCC)") (class "Default")
      (node (ref "C0") (pin "1") (pinfunction "1_1") (pintype "passive"))
      (node (ref "R4") (pin "2") (pinfunction "2_2") (pintype "passive"))
      (node (ref "U5") (pin "3") (pinfunction "VCC_3") (pintype "passive"))
    )
    (net (code "96") (name "Net-(U6-CR)") (class "Default")
      (node (ref "R12") (pin "1") (pinfunction "1_1") (pintype "passive"))
      (node (ref "U6") (pin "9") (pinfunction "CR_9") (pintype "passive"))
    )
    (net (code "97") (name "VCC5V") (class "Default")
      (node (ref "C13") (pin "2") (pinfunction "2_2") (pintype "passive"))
      (node (ref "C14") (pin "1") (pinfunction "1_1") (pintype "passive"))
      (node (ref "C3") (pin "1") (pinfunction "1_1") (pintype "passive"))
      (node (ref "C4") (pin "2") (pinfunction "2_2") (pintype "passive"))
      (node (ref "C5") (pin "2") (pinfunction "2_2") (pintype "passive"))
      (node (ref "C6") (pin "1") (pinfunction "1_1") (pintype "passive"))
      (node (ref "L1") (pin "1") (pinfunction "1_1") (pintype "passive"))
      (node (ref "P13") (pin "1") (pinfunction "1_1") (pintype "passive"))
      (node (ref "P13") (pin "2") (pinfunction "2_2") (pintype "passive"))
      (node (ref "P2") (pin "1") (pinfunction "1_1") (pintype "passive"))
      (node (ref "P7") (pin "7") (pinfunction "7_7") (pintype "passive"))
      (node (ref "R15") (pin "2") (pinfunction "2_2") (pintype "passive"))
      (node (ref "R8") (pin "2") (pinfunction "2_2") (pintype "passive"))
      (node (ref "U2") (pin "1") (pinfunction "IN_1") (pintype "passive"))
      (node (ref "U4") (pin "1") (pinfunction "IN_1") (pintype "passive"))
      (node (ref "U6") (pin "5") (pinfunction "5V_5") (pintype "passive"))
      (node (ref "U6") (pin "6") (pinfunction "5V_6") (pintype "passive"))
    )
    (net (code "98") (name "VCCBAT") (class "Default")
      (node (ref "D1") (pin "1") (pinfunction "A_1") (pintype "passive"))
      (node (ref "D2") (pin "1") (pinfunction "A_1") (pintype "passive"))
      (node (ref "P10") (pin "1") (pinfunction "VCC_1") (pintype "passive"))
      (node (ref "S6") (pin "1") (pinfunction "1_1") (pintype "passive"))
      (node (ref "S6") (pin "2") (pinfunction "2_2") (pintype "passive"))
    )
    (net (code "99") (name "VCCServo") (class "Default")
      (node (ref "C11") (pin "2") (pinfunction "2_2") (pintype "passive"))
      (node (ref "C12") (pin "1") (pinfunction "1_1") (pintype "passive"))
      (node (ref "P3") (pin "2") (pinfunction "2_2") (pintype "passive"))
      (node (ref "R6") (pin "2") (pinfunction "2_2") (pintype "passive"))
      (node (ref "R9") (pin "2") (pinfunction "2_2") (pintype "passive"))
      (node (ref "U3") (pin "5") (pinfunction "OUT_5") (pintype "passive"))
    )
    (net (code "100") (name "unconnected-(P4-Pad5)") (class "Default")
      (node (ref "P4") (pin "5") (pinfunction "5_5") (pintype "passive+no_connect"))
    )
    (net (code "101") (name "unconnected-(P4-Pad6)") (class "Default")
      (node (ref "P4") (pin "6") (pinfunction "6_6") (pintype "passive+no_connect"))
    )
    (net (code "102") (name "unconnected-(P5-Pad5)") (class "Default")
      (node (ref "P5") (pin "5") (pinfunction "5_5") (pintype "passive+no_connect"))
    )
    (net (code "103") (name "unconnected-(P5-Pad6)") (class "Default")
      (node (ref "P5") (pin "6") (pinfunction "6_6") (pintype "passive+no_connect"))
    )
    (net (code "104") (name "unconnected-(P7-Pad2)") (class "Default")
      (node (ref "P7") (pin "2") (pinfunction "2_2") (pintype "passive+no_connect"))
    )
    (net (code "105") (name "unconnected-(P7-Pad8)") (class "Default")
      (node (ref "P7") (pin "8") (pinfunction "8_8") (pintype "passive+no_connect"))
    )
    (net (code "106") (name "unconnected-(P8-Pad7)") (class "Default")
      (node (ref "P8") (pin "7") (pinfunction "7_7") (pintype "passive+no_connect"))
    )
    (net (code "107") (name "unconnected-(P8-Pad8)") (class "Default")
      (node (ref "P8") (pin "8") (pinfunction "8_8") (pintype "passive+no_connect"))
    )
    (net (code "108") (name "unconnected-(U2-NC-Pad4)") (class "Default")
      (node (ref "U2") (pin "4") (pinfunction "NC_4") (pintype "passive+no_connect"))
    )
    (net (code "109") (name "unconnected-(U4-NC-Pad4)") (class "Default")
      (node (ref "U4") (pin "4") (pinfunction "NC_4") (pintype "passive+no_connect"))
    )
    (net (code "110") (name "unconnected-(U6-2DN-Pad22)") (class "Default")
      (node (ref "U6") (pin "22") (pinfunction "2DN_22") (pintype "passive+no_connect"))
    )
    (net (code "111") (name "unconnected-(U6-2DP-Pad21)") (class "Default")
      (node (ref "U6") (pin "21") (pinfunction "2DP_21") (pintype "passive+no_connect"))
    )
    (net (code "112") (name "unconnected-(U6-3V3-Pad3)") (class "Default")
      (node (ref "U6") (pin "3") (pinfunction "3V3_3") (pintype "passive+no_connect"))
    )
    (net (code "113") (name "unconnected-(U6-3V3-Pad4)") (class "Default")
      (node (ref "U6") (pin "4") (pinfunction "3V3_4") (pintype "passive+no_connect"))
    )
    (net (code "114") (name "unconnected-(U6-OF-Pad7)") (class "Default")
      (node (ref "U6") (pin "7") (pinfunction "OF_7") (pintype "passive+no_connect"))
    )
    (net (code "115") (name "unconnected-(U6-WU-Pad8)") (class "Default")
      (node (ref "U6") (pin "8") (pinfunction "WU_8") (pintype "passive+no_connect"))
    )
  )
)
